# socket-v2-low-voltage.net
KiCad netlist of a schematic drawn in EAGLE
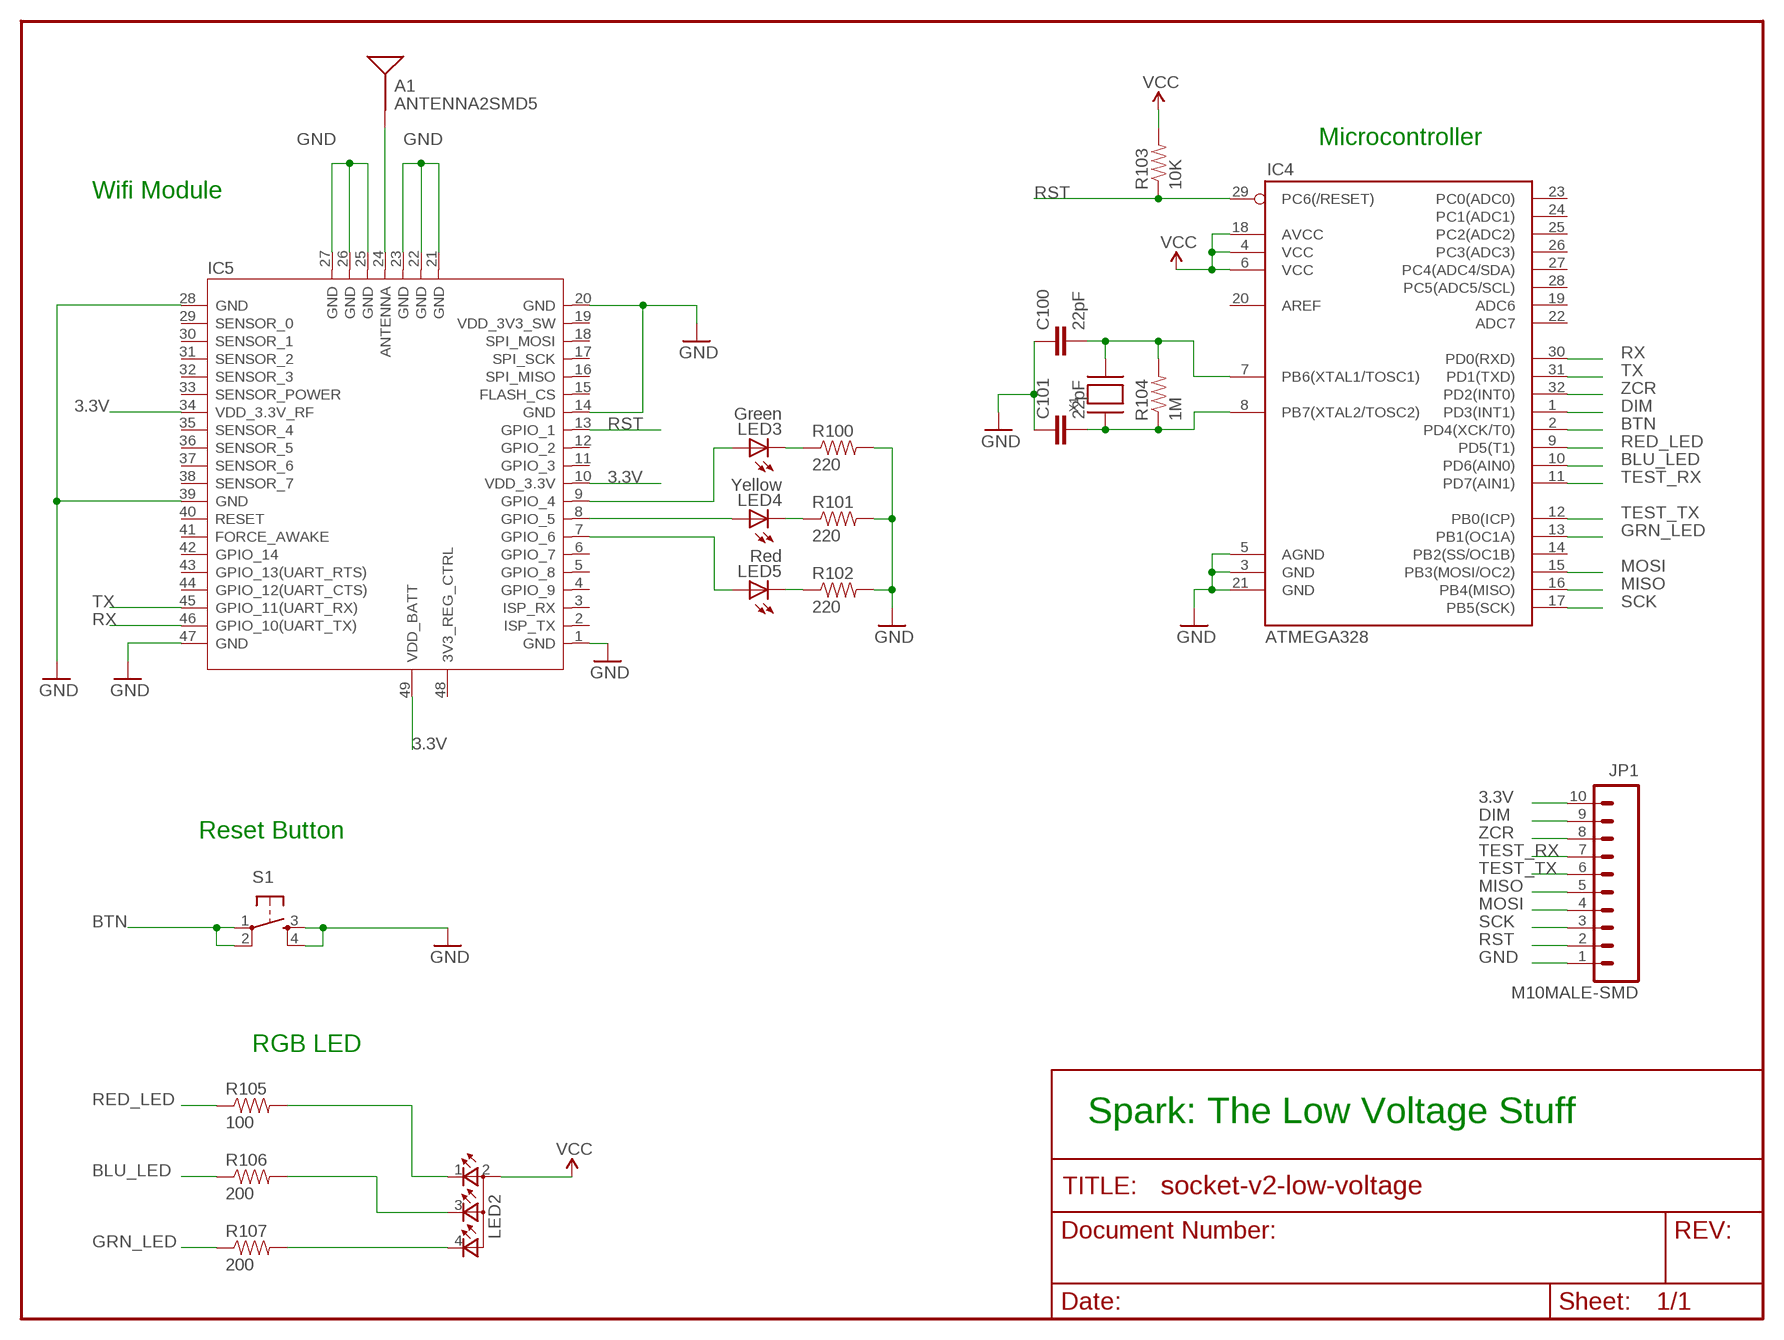
[diagram p0: schematic, sheet 1]

(export (version "E")
  (design (tool "Eeschema 10.0.6"))
  (components
    (comp (ref "A1")
      (value "ANTENNA2SMD5")
      (footprint "eagle-import:ANTENNA-CHIP5")
      (libsource (lib "eagle-import") (part "ANTENNA2SMD5"))
    )
    (comp (ref "C100")
      (value "22pF")
      (footprint "eagle-import:0603-CAP")
      (libsource (lib "eagle-import") (part "CAP0603-CAP"))
    )
    (comp (ref "C101")
      (value "22pF")
      (footprint "eagle-import:0603-CAP")
      (libsource (lib "eagle-import") (part "CAP0603-CAP"))
    )
    (comp (ref "IC4")
      (value "ATMEGA328")
      (footprint "eagle-import:TQFP32-08")
      (libsource (lib "eagle-import") (part "ATMEGA168"))
    )
    (comp (ref "IC5")
      (value "WIFI-RN-171")
      (footprint "eagle-import:49P-1.27-26.67X17.78")
      (libsource (lib "eagle-import") (part "WIFI-RN-171"))
    )
    (comp (ref "JP1")
      (value "M10MALE-SMD")
      (footprint "eagle-import:1X10-2MM-MALE-SMD")
      (libsource (lib "eagle-import") (part "M10MALE-SMD"))
    )
    (comp (ref "LED2")
      (value "TOPLED-3PLCC")
      (footprint "eagle-import:P-LCC-4-3")
      (libsource (lib "eagle-import") (part "TOPLED-3PLCC"))
    )
    (comp (ref "LED3")
      (value "Green")
      (footprint "eagle-import:LED-0603")
      (libsource (lib "eagle-import") (part "LED0603"))
    )
    (comp (ref "LED4")
      (value "Yellow")
      (footprint "eagle-import:LED-0603")
      (libsource (lib "eagle-import") (part "LED0603"))
    )
    (comp (ref "LED5")
      (value "Red")
      (footprint "eagle-import:LED-0603")
      (libsource (lib "eagle-import") (part "LED0603"))
    )
    (comp (ref "R100")
      (value "220")
      (footprint "eagle-import:0603-RES")
      (libsource (lib "eagle-import") (part "RESISTOR0603-RES"))
    )
    (comp (ref "R101")
      (value "220")
      (footprint "eagle-import:0603-RES")
      (libsource (lib "eagle-import") (part "RESISTOR0603-RES"))
    )
    (comp (ref "R102")
      (value "220")
      (footprint "eagle-import:0603-RES")
      (libsource (lib "eagle-import") (part "RESISTOR0603-RES"))
    )
    (comp (ref "R103")
      (value "10K")
      (footprint "eagle-import:0603-RES")
      (libsource (lib "eagle-import") (part "RESISTOR0603-RES"))
    )
    (comp (ref "R104")
      (value "1M")
      (footprint "eagle-import:0603-RES")
      (libsource (lib "eagle-import") (part "RESISTOR0603-RES"))
    )
    (comp (ref "R105")
      (value "100")
      (footprint "eagle-import:0603-RES")
      (libsource (lib "eagle-import") (part "RESISTOR0603-RES"))
    )
    (comp (ref "R106")
      (value "200")
      (footprint "eagle-import:0603-RES")
      (libsource (lib "eagle-import") (part "RESISTOR0603-RES"))
    )
    (comp (ref "R107")
      (value "200")
      (footprint "eagle-import:0603-RES")
      (libsource (lib "eagle-import") (part "RESISTOR0603-RES"))
    )
    (comp (ref "S1")
      (value "TAC_SWITCHSMD")
      (footprint "eagle-import:TACTILE_SWITCH_SMD")
      (libsource (lib "eagle-import") (part "TAC_SWITCHSMD"))
    )
    (comp (ref "X1")
      (value "XTALNX5032")
      (footprint "eagle-import:NX5032")
      (libsource (lib "eagle-import") (part "XTALNX5032"))
    )
  )
  (nets
    (net (code "1") (name "/BLU_LED") (class "Default")
      (node (ref "IC4") (pin "10") (pinfunction "PD6(AIN0)_10") (pintype "bidirectional"))
      (node (ref "R106") (pin "1") (pinfunction "1_1") (pintype "passive"))
    )
    (net (code "2") (name "/BTN") (class "Default")
      (node (ref "IC4") (pin "2") (pinfunction "PD4(XCK/T0)_2") (pintype "bidirectional"))
      (node (ref "S1") (pin "1") (pinfunction "1_1") (pintype "passive"))
      (node (ref "S1") (pin "2") (pinfunction "2_2") (pintype "passive"))
    )
    (net (code "3") (name "/DIM") (class "Default")
      (node (ref "IC4") (pin "1") (pinfunction "PD3(INT1)_1") (pintype "bidirectional"))
      (node (ref "JP1") (pin "9") (pinfunction "9_9") (pintype "passive"))
    )
    (net (code "4") (name "/GRN_LED") (class "Default")
      (node (ref "IC4") (pin "13") (pinfunction "PB1(OC1A)_13") (pintype "bidirectional"))
      (node (ref "R107") (pin "1") (pinfunction "1_1") (pintype "passive"))
    )
    (net (code "5") (name "/MISO") (class "Default")
      (node (ref "IC4") (pin "16") (pinfunction "PB4(MISO)_16") (pintype "bidirectional"))
      (node (ref "JP1") (pin "5") (pinfunction "5_5") (pintype "passive"))
    )
    (net (code "6") (name "/MOSI") (class "Default")
      (node (ref "IC4") (pin "15") (pinfunction "PB3(MOSI/OC2)_15") (pintype "bidirectional"))
      (node (ref "JP1") (pin "4") (pinfunction "4_4") (pintype "passive"))
    )
    (net (code "7") (name "/RED_LED") (class "Default")
      (node (ref "IC4") (pin "9") (pinfunction "PD5(T1)_9") (pintype "bidirectional"))
      (node (ref "R105") (pin "1") (pinfunction "1_1") (pintype "passive"))
    )
    (net (code "8") (name "/RST") (class "Default")
      (node (ref "IC4") (pin "29") (pinfunction "PC6(/RESET)_29") (pintype "bidirectional"))
      (node (ref "IC5") (pin "13") (pinfunction "GPIO_1_13") (pintype "bidirectional"))
      (node (ref "JP1") (pin "2") (pinfunction "2_2") (pintype "passive"))
      (node (ref "R103") (pin "1") (pinfunction "1_1") (pintype "passive"))
    )
    (net (code "9") (name "/RX") (class "Default")
      (node (ref "IC4") (pin "30") (pinfunction "PD0(RXD)_30") (pintype "bidirectional"))
      (node (ref "IC5") (pin "46") (pinfunction "GPIO_10(UART_TX)_46") (pintype "bidirectional"))
    )
    (net (code "10") (name "/SCK") (class "Default")
      (node (ref "IC4") (pin "17") (pinfunction "PB5(SCK)_17") (pintype "bidirectional"))
      (node (ref "JP1") (pin "3") (pinfunction "3_3") (pintype "passive"))
    )
    (net (code "11") (name "/TEST_RX") (class "Default")
      (node (ref "IC4") (pin "11") (pinfunction "PD7(AIN1)_11") (pintype "bidirectional"))
      (node (ref "JP1") (pin "7") (pinfunction "7_7") (pintype "passive"))
    )
    (net (code "12") (name "/TEST_TX") (class "Default")
      (node (ref "IC4") (pin "12") (pinfunction "PB0(ICP)_12") (pintype "bidirectional"))
      (node (ref "JP1") (pin "6") (pinfunction "6_6") (pintype "passive"))
    )
    (net (code "13") (name "/TX") (class "Default")
      (node (ref "IC4") (pin "31") (pinfunction "PD1(TXD)_31") (pintype "bidirectional"))
      (node (ref "IC5") (pin "45") (pinfunction "GPIO_11(UART_RX)_45") (pintype "bidirectional"))
    )
    (net (code "14") (name "/ZCR") (class "Default")
      (node (ref "IC4") (pin "32") (pinfunction "PD2(INT0)_32") (pintype "bidirectional"))
      (node (ref "JP1") (pin "8") (pinfunction "8_8") (pintype "passive"))
    )
    (net (code "15") (name "GND") (class "Default")
      (node (ref "C100") (pin "1") (pinfunction "1_1") (pintype "passive"))
      (node (ref "C101") (pin "1") (pinfunction "1_1") (pintype "passive"))
      (node (ref "IC4") (pin "21") (pinfunction "GND_21") (pintype "bidirectional"))
      (node (ref "IC4") (pin "3") (pinfunction "GND_3") (pintype "bidirectional"))
      (node (ref "IC4") (pin "5") (pinfunction "AGND_5") (pintype "bidirectional"))
      (node (ref "IC5") (pin "1") (pinfunction "GND_1") (pintype "power_in"))
      (node (ref "IC5") (pin "14") (pinfunction "GND_14") (pintype "power_in"))
      (node (ref "IC5") (pin "20") (pinfunction "GND_20") (pintype "power_in"))
      (node (ref "IC5") (pin "21") (pinfunction "GND_21") (pintype "power_in"))
      (node (ref "IC5") (pin "22") (pinfunction "GND_22") (pintype "power_in"))
      (node (ref "IC5") (pin "23") (pinfunction "GND_23") (pintype "power_in"))
      (node (ref "IC5") (pin "25") (pinfunction "GND_25") (pintype "power_in"))
      (node (ref "IC5") (pin "26") (pinfunction "GND_26") (pintype "power_in"))
      (node (ref "IC5") (pin "27") (pinfunction "GND_27") (pintype "power_in"))
      (node (ref "IC5") (pin "28") (pinfunction "GND_28") (pintype "power_in"))
      (node (ref "IC5") (pin "39") (pinfunction "GND_39") (pintype "power_in"))
      (node (ref "IC5") (pin "47") (pinfunction "GND_47") (pintype "power_in"))
      (node (ref "JP1") (pin "1") (pinfunction "1_1") (pintype "passive"))
      (node (ref "R100") (pin "2") (pinfunction "2_2") (pintype "passive"))
      (node (ref "R101") (pin "2") (pinfunction "2_2") (pintype "passive"))
      (node (ref "R102") (pin "2") (pinfunction "2_2") (pintype "passive"))
      (node (ref "S1") (pin "3") (pinfunction "3_3") (pintype "passive"))
      (node (ref "S1") (pin "4") (pinfunction "4_4") (pintype "passive"))
    )
    (net (code "16") (name "Net-(A1-SIGNAL)") (class "Default")
      (node (ref "A1") (pin "FEED") (pinfunction "SIGNAL_FEED") (pintype "bidirectional"))
      (node (ref "IC5") (pin "24") (pinfunction "ANTENNA_24") (pintype "bidirectional"))
    )
    (net (code "17") (name "Net-(IC4-PB6(XTAL1{slash}TOSC1))") (class "Default")
      (node (ref "C100") (pin "2") (pinfunction "2_2") (pintype "passive"))
      (node (ref "IC4") (pin "7") (pinfunction "PB6(XTAL1/TOSC1)_7") (pintype "bidirectional"))
      (node (ref "R104") (pin "2") (pinfunction "2_2") (pintype "passive"))
      (node (ref "X1") (pin "P$2") (pinfunction "P$2_P$2") (pintype "bidirectional"))
    )
    (net (code "18") (name "Net-(IC4-PB7(XTAL2{slash}TOSC2))") (class "Default")
      (node (ref "C101") (pin "2") (pinfunction "2_2") (pintype "passive"))
      (node (ref "IC4") (pin "8") (pinfunction "PB7(XTAL2/TOSC2)_8") (pintype "bidirectional"))
      (node (ref "R104") (pin "1") (pinfunction "1_1") (pintype "passive"))
      (node (ref "X1") (pin "P$1") (pinfunction "P$1_P$1") (pintype "bidirectional"))
    )
    (net (code "19") (name "Net-(IC5-GPIO_4)") (class "Default")
      (node (ref "IC5") (pin "9") (pinfunction "GPIO_4_9") (pintype "bidirectional"))
      (node (ref "LED3") (pin "A") (pinfunction "A_A") (pintype "passive"))
    )
    (net (code "20") (name "Net-(IC5-GPIO_5)") (class "Default")
      (node (ref "IC5") (pin "8") (pinfunction "GPIO_5_8") (pintype "bidirectional"))
      (node (ref "LED4") (pin "A") (pinfunction "A_A") (pintype "passive"))
    )
    (net (code "21") (name "Net-(IC5-GPIO_6)") (class "Default")
      (node (ref "IC5") (pin "7") (pinfunction "GPIO_6_7") (pintype "bidirectional"))
      (node (ref "LED5") (pin "A") (pinfunction "A_A") (pintype "passive"))
    )
    (net (code "22") (name "Net-(LED2-CBLUE)") (class "Default")
      (node (ref "LED2") (pin "3") (pinfunction "CBLUE_3") (pintype "passive"))
      (node (ref "R106") (pin "2") (pinfunction "2_2") (pintype "passive"))
    )
    (net (code "23") (name "Net-(LED2-CGREEN)") (class "Default")
      (node (ref "LED2") (pin "4") (pinfunction "CGREEN_4") (pintype "passive"))
      (node (ref "R107") (pin "2") (pinfunction "2_2") (pintype "passive"))
    )
    (net (code "24") (name "Net-(LED2-CRED)") (class "Default")
      (node (ref "LED2") (pin "1") (pinfunction "CRED_1") (pintype "passive"))
      (node (ref "R105") (pin "2") (pinfunction "2_2") (pintype "passive"))
    )
    (net (code "25") (name "Net-(LED3-PadC)") (class "Default")
      (node (ref "LED3") (pin "C") (pinfunction "C_C") (pintype "passive"))
      (node (ref "R100") (pin "1") (pinfunction "1_1") (pintype "passive"))
    )
    (net (code "26") (name "Net-(LED4-PadC)") (class "Default")
      (node (ref "LED4") (pin "C") (pinfunction "C_C") (pintype "passive"))
      (node (ref "R101") (pin "1") (pinfunction "1_1") (pintype "passive"))
    )
    (net (code "27") (name "Net-(LED5-PadC)") (class "Default")
      (node (ref "LED5") (pin "C") (pinfunction "C_C") (pintype "passive"))
      (node (ref "R102") (pin "1") (pinfunction "1_1") (pintype "passive"))
    )
    (net (code "28") (name "VCC") (class "Default")
      (node (ref "IC4") (pin "18") (pinfunction "AVCC_18") (pintype "bidirectional"))
      (node (ref "IC4") (pin "4") (pinfunction "VCC_4") (pintype "bidirectional"))
      (node (ref "IC4") (pin "6") (pinfunction "VCC_6") (pintype "bidirectional"))
      (node (ref "IC5") (pin "10") (pinfunction "VDD_3.3V_10") (pintype "power_in"))
      (node (ref "IC5") (pin "34") (pinfunction "VDD_3.3V_RF_34") (pintype "power_in"))
      (node (ref "IC5") (pin "49") (pinfunction "VDD_BATT_49") (pintype "bidirectional"))
      (node (ref "JP1") (pin "10") (pinfunction "10_10") (pintype "passive"))
      (node (ref "LED2") (pin "2") (pinfunction "A2_2") (pintype "passive"))
      (node (ref "R103") (pin "2") (pinfunction "2_2") (pintype "passive"))
    )
    (net (code "29") (name "unconnected-(IC4-ADC6-Pad19)") (class "Default")
      (node (ref "IC4") (pin "19") (pinfunction "ADC6_19") (pintype "bidirectional"))
    )
    (net (code "30") (name "unconnected-(IC4-ADC7-Pad22)") (class "Default")
      (node (ref "IC4") (pin "22") (pinfunction "ADC7_22") (pintype "bidirectional"))
    )
    (net (code "31") (name "unconnected-(IC4-AREF-Pad20)") (class "Default")
      (node (ref "IC4") (pin "20") (pinfunction "AREF_20") (pintype "bidirectional"))
    )
    (net (code "32") (name "unconnected-(IC4-PB2(SS{slash}OC1B)-Pad14)") (class "Default")
      (node (ref "IC4") (pin "14") (pinfunction "PB2(SS/OC1B)_14") (pintype "bidirectional"))
    )
    (net (code "33") (name "unconnected-(IC4-PC0(ADC0)-Pad23)") (class "Default")
      (node (ref "IC4") (pin "23") (pinfunction "PC0(ADC0)_23") (pintype "bidirectional"))
    )
    (net (code "34") (name "unconnected-(IC4-PC1(ADC1)-Pad24)") (class "Default")
      (node (ref "IC4") (pin "24") (pinfunction "PC1(ADC1)_24") (pintype "bidirectional"))
    )
    (net (code "35") (name "unconnected-(IC4-PC2(ADC2)-Pad25)") (class "Default")
      (node (ref "IC4") (pin "25") (pinfunction "PC2(ADC2)_25") (pintype "bidirectional"))
    )
    (net (code "36") (name "unconnected-(IC4-PC3(ADC3)-Pad26)") (class "Default")
      (node (ref "IC4") (pin "26") (pinfunction "PC3(ADC3)_26") (pintype "bidirectional"))
    )
    (net (code "37") (name "unconnected-(IC4-PC4(ADC4{slash}SDA)-Pad27)") (class "Default")
      (node (ref "IC4") (pin "27") (pinfunction "PC4(ADC4/SDA)_27") (pintype "bidirectional"))
    )
    (net (code "38") (name "unconnected-(IC4-PC5(ADC5{slash}SCL)-Pad28)") (class "Default")
      (node (ref "IC4") (pin "28") (pinfunction "PC5(ADC5/SCL)_28") (pintype "bidirectional"))
    )
    (net (code "39") (name "unconnected-(IC5-3V3_REG_CTRL-Pad48)") (class "Default")
      (node (ref "IC5") (pin "48") (pinfunction "3V3_REG_CTRL_48") (pintype "input"))
    )
    (net (code "40") (name "unconnected-(IC5-FLASH_CS-Pad15)") (class "Default")
      (node (ref "IC5") (pin "15") (pinfunction "FLASH_CS_15") (pintype "bidirectional"))
    )
    (net (code "41") (name "unconnected-(IC5-FORCE_AWAKE-Pad41)") (class "Default")
      (node (ref "IC5") (pin "41") (pinfunction "FORCE_AWAKE_41") (pintype "bidirectional"))
    )
    (net (code "42") (name "unconnected-(IC5-GPIO_2-Pad12)") (class "Default")
      (node (ref "IC5") (pin "12") (pinfunction "GPIO_2_12") (pintype "bidirectional"))
    )
    (net (code "43") (name "unconnected-(IC5-GPIO_3-Pad11)") (class "Default")
      (node (ref "IC5") (pin "11") (pinfunction "GPIO_3_11") (pintype "bidirectional"))
    )
    (net (code "44") (name "unconnected-(IC5-GPIO_7-Pad6)") (class "Default")
      (node (ref "IC5") (pin "6") (pinfunction "GPIO_7_6") (pintype "bidirectional"))
    )
    (net (code "45") (name "unconnected-(IC5-GPIO_8-Pad5)") (class "Default")
      (node (ref "IC5") (pin "5") (pinfunction "GPIO_8_5") (pintype "bidirectional"))
    )
    (net (code "46") (name "unconnected-(IC5-GPIO_9-Pad4)") (class "Default")
      (node (ref "IC5") (pin "4") (pinfunction "GPIO_9_4") (pintype "bidirectional"))
    )
    (net (code "47") (name "unconnected-(IC5-GPIO_12(UART_CTS)-Pad44)") (class "Default")
      (node (ref "IC5") (pin "44") (pinfunction "GPIO_12(UART_CTS)_44") (pintype "bidirectional"))
    )
    (net (code "48") (name "unconnected-(IC5-GPIO_13(UART_RTS)-Pad43)") (class "Default")
      (node (ref "IC5") (pin "43") (pinfunction "GPIO_13(UART_RTS)_43") (pintype "bidirectional"))
    )
    (net (code "49") (name "unconnected-(IC5-GPIO_14-Pad42)") (class "Default")
      (node (ref "IC5") (pin "42") (pinfunction "GPIO_14_42") (pintype "bidirectional"))
    )
    (net (code "50") (name "unconnected-(IC5-ISP_RX-Pad3)") (class "Default")
      (node (ref "IC5") (pin "3") (pinfunction "ISP_RX_3") (pintype "bidirectional"))
    )
    (net (code "51") (name "unconnected-(IC5-ISP_TX-Pad2)") (class "Default")
      (node (ref "IC5") (pin "2") (pinfunction "ISP_TX_2") (pintype "bidirectional"))
    )
    (net (code "52") (name "unconnected-(IC5-RESET-Pad40)") (class "Default")
      (node (ref "IC5") (pin "40") (pinfunction "RESET_40") (pintype "input"))
    )
    (net (code "53") (name "unconnected-(IC5-SENSOR_0-Pad29)") (class "Default")
      (node (ref "IC5") (pin "29") (pinfunction "SENSOR_0_29") (pintype "input"))
    )
    (net (code "54") (name "unconnected-(IC5-SENSOR_1-Pad30)") (class "Default")
      (node (ref "IC5") (pin "30") (pinfunction "SENSOR_1_30") (pintype "input"))
    )
    (net (code "55") (name "unconnected-(IC5-SENSOR_2-Pad31)") (class "Default")
      (node (ref "IC5") (pin "31") (pinfunction "SENSOR_2_31") (pintype "input"))
    )
    (net (code "56") (name "unconnected-(IC5-SENSOR_3-Pad32)") (class "Default")
      (node (ref "IC5") (pin "32") (pinfunction "SENSOR_3_32") (pintype "input"))
    )
    (net (code "57") (name "unconnected-(IC5-SENSOR_4-Pad35)") (class "Default")
      (node (ref "IC5") (pin "35") (pinfunction "SENSOR_4_35") (pintype "input"))
    )
    (net (code "58") (name "unconnected-(IC5-SENSOR_5-Pad36)") (class "Default")
      (node (ref "IC5") (pin "36") (pinfunction "SENSOR_5_36") (pintype "input"))
    )
    (net (code "59") (name "unconnected-(IC5-SENSOR_6-Pad37)") (class "Default")
      (node (ref "IC5") (pin "37") (pinfunction "SENSOR_6_37") (pintype "input"))
    )
    (net (code "60") (name "unconnected-(IC5-SENSOR_7-Pad38)") (class "Default")
      (node (ref "IC5") (pin "38") (pinfunction "SENSOR_7_38") (pintype "input"))
    )
    (net (code "61") (name "unconnected-(IC5-SENSOR_POWER-Pad33)") (class "Default")
      (node (ref "IC5") (pin "33") (pinfunction "SENSOR_POWER_33") (pintype "output"))
    )
    (net (code "62") (name "unconnected-(IC5-SPI_MISO-Pad16)") (class "Default")
      (node (ref "IC5") (pin "16") (pinfunction "SPI_MISO_16") (pintype "bidirectional"))
    )
    (net (code "63") (name "unconnected-(IC5-SPI_MOSI-Pad18)") (class "Default")
      (node (ref "IC5") (pin "18") (pinfunction "SPI_MOSI_18") (pintype "bidirectional"))
    )
    (net (code "64") (name "unconnected-(IC5-SPI_SCK-Pad17)") (class "Default")
      (node (ref "IC5") (pin "17") (pinfunction "SPI_SCK_17") (pintype "bidirectional"))
    )
    (net (code "65") (name "unconnected-(IC5-VDD_3V3_SW-Pad19)") (class "Default")
      (node (ref "IC5") (pin "19") (pinfunction "VDD_3V3_SW_19") (pintype "bidirectional"))
    )
  )
)
